# CanarySchematic3_0.net
KiCad netlist of a schematic drawn in EAGLE
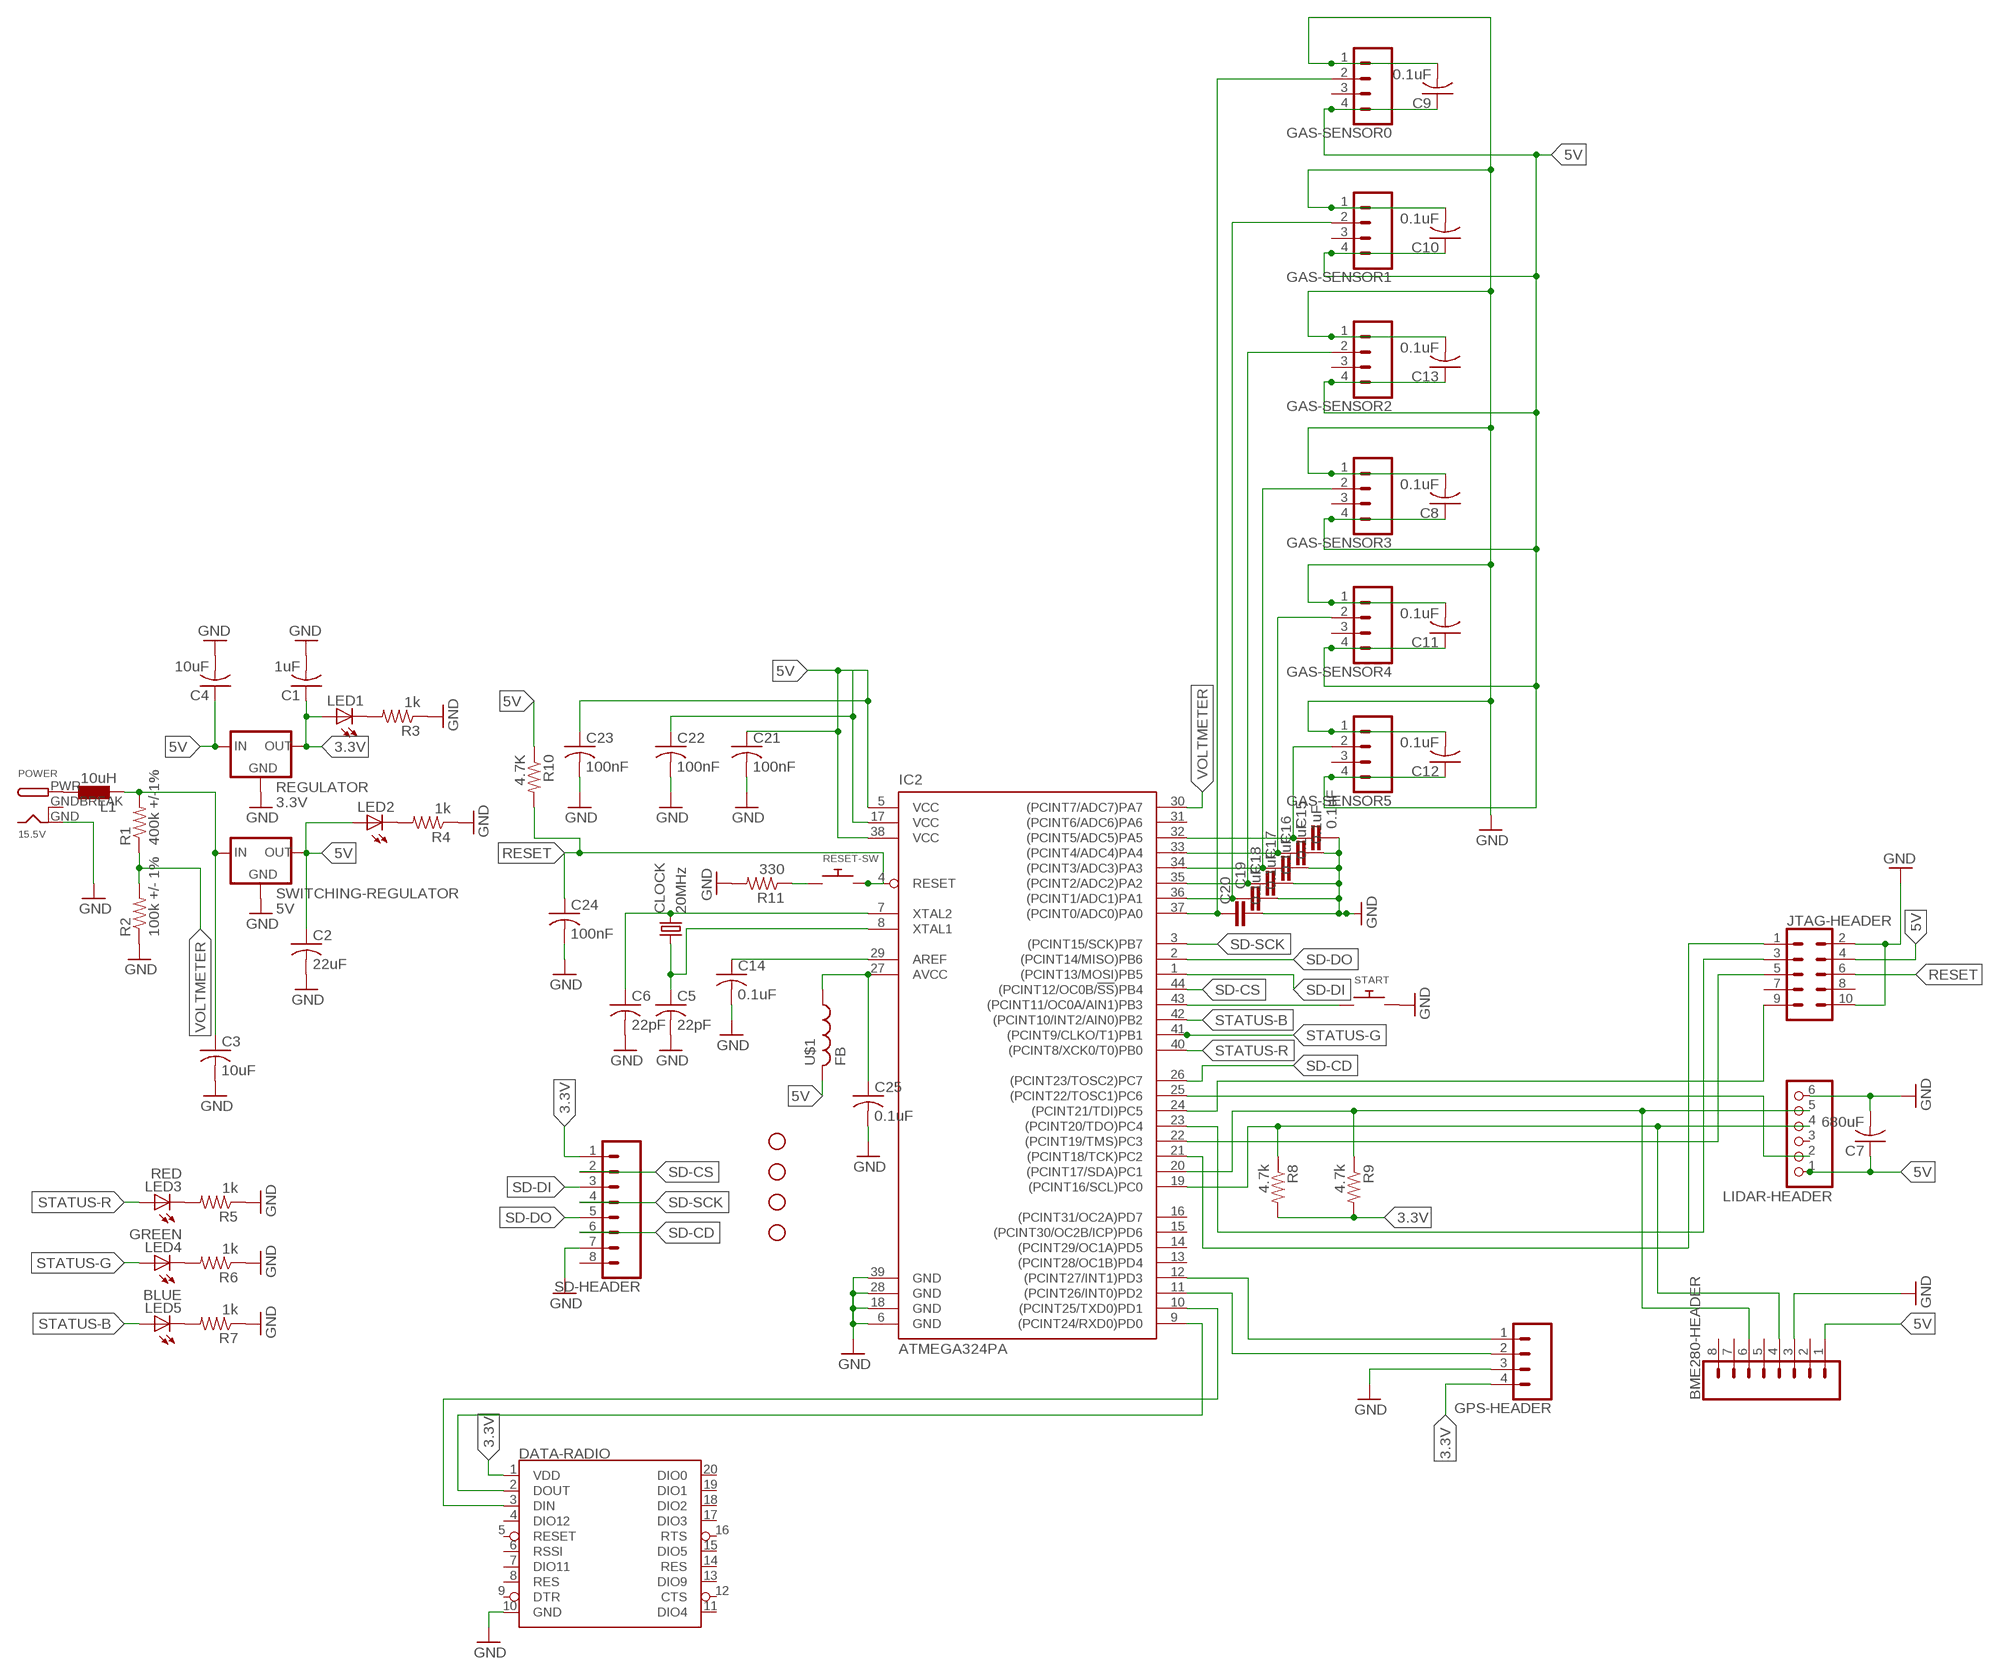
[diagram p0: schematic, sheet 1]

(export (version "E")
  (design (tool "Eeschema 10.0.6"))
  (components
    (comp (ref "BME280-HEADER")
      (value "CONN_08\"")
      (footprint "eagle-import:1X08")
      (libsource (lib "eagle-import") (part "CONN_08{dblquote}"))
    )
    (comp (ref "C1")
      (value "1uF")
      (footprint "eagle-import:C0805")
      (libsource (lib "eagle-import") (part "C-USC0805"))
    )
    (comp (ref "C2")
      (value "22uF")
      (footprint "eagle-import:C0805")
      (libsource (lib "eagle-import") (part "C-USC0805"))
    )
    (comp (ref "C3")
      (value "10uF")
      (footprint "eagle-import:C0805")
      (libsource (lib "eagle-import") (part "C-USC0805"))
    )
    (comp (ref "C4")
      (value "10uF")
      (footprint "eagle-import:C0805")
      (libsource (lib "eagle-import") (part "C-USC0805"))
    )
    (comp (ref "C5")
      (value "22pF")
      (footprint "eagle-import:C0805")
      (libsource (lib "eagle-import") (part "C-USC0805"))
    )
    (comp (ref "C6")
      (value "22pF")
      (footprint "eagle-import:C0805")
      (libsource (lib "eagle-import") (part "C-USC0805"))
    )
    (comp (ref "C7")
      (value "680uF")
      (footprint "eagle-import:C0805")
      (libsource (lib "eagle-import") (part "C-USC0805"))
    )
    (comp (ref "C8")
      (value "0.1uF")
      (footprint "eagle-import:C0805")
      (libsource (lib "eagle-import") (part "C-USC0805"))
    )
    (comp (ref "C9")
      (value "0.1uF")
      (footprint "eagle-import:C0805")
      (libsource (lib "eagle-import") (part "C-USC0805"))
    )
    (comp (ref "C10")
      (value "0.1uF")
      (footprint "eagle-import:C0805")
      (libsource (lib "eagle-import") (part "C-USC0805"))
    )
    (comp (ref "C11")
      (value "0.1uF")
      (footprint "eagle-import:C0805")
      (libsource (lib "eagle-import") (part "C-USC0805"))
    )
    (comp (ref "C12")
      (value "0.1uF")
      (footprint "eagle-import:C0805")
      (libsource (lib "eagle-import") (part "C-USC0805"))
    )
    (comp (ref "C13")
      (value "0.1uF")
      (footprint "eagle-import:C0805")
      (libsource (lib "eagle-import") (part "C-USC0805"))
    )
    (comp (ref "C14")
      (value "0.1uF")
      (footprint "eagle-import:C0805")
      (libsource (lib "eagle-import") (part "C-USC0805"))
    )
    (comp (ref "C15")
      (value "0.1uF")
      (footprint "eagle-import:C0504")
      (libsource (lib "eagle-import") (part "CC0504"))
    )
    (comp (ref "C16")
      (value "0.1uF")
      (footprint "eagle-import:C0504")
      (libsource (lib "eagle-import") (part "CC0504"))
    )
    (comp (ref "C17")
      (value "0.1uF")
      (footprint "eagle-import:C0504")
      (libsource (lib "eagle-import") (part "CC0504"))
    )
    (comp (ref "C18")
      (value "0.1uF")
      (footprint "eagle-import:C0504")
      (libsource (lib "eagle-import") (part "CC0504"))
    )
    (comp (ref "C19")
      (value "0.1uF")
      (footprint "eagle-import:C0504")
      (libsource (lib "eagle-import") (part "CC0504"))
    )
    (comp (ref "C20")
      (value "0.1uF")
      (footprint "eagle-import:C0504")
      (libsource (lib "eagle-import") (part "CC0504"))
    )
    (comp (ref "C21")
      (value "100nF")
      (footprint "eagle-import:C0805")
      (libsource (lib "eagle-import") (part "C-USC0805"))
    )
    (comp (ref "C22")
      (value "100nF")
      (footprint "eagle-import:C0805")
      (libsource (lib "eagle-import") (part "C-USC0805"))
    )
    (comp (ref "C23")
      (value "100nF")
      (footprint "eagle-import:C0805")
      (libsource (lib "eagle-import") (part "C-USC0805"))
    )
    (comp (ref "C24")
      (value "100nF")
      (footprint "eagle-import:C0805")
      (libsource (lib "eagle-import") (part "C-USC0805"))
    )
    (comp (ref "C25")
      (value "0.1uF")
      (footprint "eagle-import:C0805")
      (libsource (lib "eagle-import") (part "C-USC0805"))
    )
    (comp (ref "CLOCK")
      (value "20MHz")
      (footprint "eagle-import:86SMX")
      (libsource (lib "eagle-import") (part "CRYSTAL68SMX"))
    )
    (comp (ref "DATA-RADIO")
      (value "XBEE")
      (footprint "eagle-import:XBEE")
      (libsource (lib "eagle-import") (part "XBEE"))
    )
    (comp (ref "GAS-SENSOR0")
      (value "CONN_04")
      (footprint "eagle-import:1X04")
      (libsource (lib "eagle-import") (part "CONN_04"))
    )
    (comp (ref "GAS-SENSOR1")
      (value "CONN_04")
      (footprint "eagle-import:1X04")
      (libsource (lib "eagle-import") (part "CONN_04"))
    )
    (comp (ref "GAS-SENSOR2")
      (value "CONN_04")
      (footprint "eagle-import:1X04")
      (libsource (lib "eagle-import") (part "CONN_04"))
    )
    (comp (ref "GAS-SENSOR3")
      (value "CONN_04")
      (footprint "eagle-import:1X04")
      (libsource (lib "eagle-import") (part "CONN_04"))
    )
    (comp (ref "GAS-SENSOR4")
      (value "CONN_04")
      (footprint "eagle-import:1X04")
      (libsource (lib "eagle-import") (part "CONN_04"))
    )
    (comp (ref "GAS-SENSOR5")
      (value "CONN_04")
      (footprint "eagle-import:1X04")
      (libsource (lib "eagle-import") (part "CONN_04"))
    )
    (comp (ref "GPS-HEADER")
      (value "CONN_04")
      (footprint "eagle-import:1X04")
      (libsource (lib "eagle-import") (part "CONN_04"))
    )
    (comp (ref "H8")
      (value "STAND-OFF")
      (footprint "eagle-import:STAND-OFF")
      (libsource (lib "eagle-import") (part "STAND-OFF"))
    )
    (comp (ref "IC2")
      (value "ATMEGA324PA")
      (footprint "eagle-import:TQFP44")
      (fields (field (name "MPN") "ATMEGA644PV-10AU"))
      (libsource (lib "eagle-import") (part "ATMEGA644A"))
    )
    (comp (ref "JTAG-HEADER")
      (value "CONN_05X2PTH")
      (footprint "eagle-import:2X5")
      (libsource (lib "eagle-import") (part "CONN_05X2PTH"))
    )
    (comp (ref "L1")
      (value "10uH")
      (footprint "eagle-import:L1812")
      (libsource (lib "eagle-import") (part "L"))
    )
    (comp (ref "LED1")
      (value "LEDCHIP-LED0805")
      (footprint "eagle-import:CHIP-LED0805")
      (libsource (lib "eagle-import") (part "LEDCHIP-LED0805"))
    )
    (comp (ref "LED2")
      (value "LEDCHIP-LED0805")
      (footprint "eagle-import:CHIP-LED0805")
      (libsource (lib "eagle-import") (part "LEDCHIP-LED0805"))
    )
    (comp (ref "LED3")
      (value "RED")
      (footprint "eagle-import:CHIP-LED0805")
      (libsource (lib "eagle-import") (part "LEDCHIP-LED0805"))
    )
    (comp (ref "LED4")
      (value "GREEN")
      (footprint "eagle-import:CHIP-LED0805")
      (libsource (lib "eagle-import") (part "LEDCHIP-LED0805"))
    )
    (comp (ref "LED5")
      (value "BLUE")
      (footprint "eagle-import:CHIP-LED0805")
      (libsource (lib "eagle-import") (part "LEDCHIP-LED0805"))
    )
    (comp (ref "LIDAR-HEADER")
      (value "PINHD-1X6")
      (footprint "eagle-import:1X06")
      (libsource (lib "eagle-import") (part "PINHD-1X6"))
    )
    (comp (ref "MOUNT-HOLE1")
      (value "STAND-OFF")
      (footprint "eagle-import:STAND-OFF")
      (libsource (lib "eagle-import") (part "STAND-OFF"))
    )
    (comp (ref "MOUNT-HOLE2")
      (value "STAND-OFF")
      (footprint "eagle-import:STAND-OFF")
      (libsource (lib "eagle-import") (part "STAND-OFF"))
    )
    (comp (ref "MOUNT-HOLE3")
      (value "STAND-OFF")
      (footprint "eagle-import:STAND-OFF")
      (libsource (lib "eagle-import") (part "STAND-OFF"))
    )
    (comp (ref "POWER")
      (value "15.5V")
      (footprint "eagle-import:DCJACK_2MM_PTH")
      (libsource (lib "eagle-import") (part "DCBARRELPTH"))
    )
    (comp (ref "R1")
      (value "400k +/-1%")
      (footprint "eagle-import:M0805")
      (libsource (lib "eagle-import") (part "R-US_M0805"))
    )
    (comp (ref "R2")
      (value "100k +/- 1%")
      (footprint "eagle-import:M0805")
      (libsource (lib "eagle-import") (part "R-US_M0805"))
    )
    (comp (ref "R3")
      (value "1k")
      (footprint "eagle-import:M0805")
      (libsource (lib "eagle-import") (part "R-US_M0805"))
    )
    (comp (ref "R4")
      (value "1k")
      (footprint "eagle-import:M0805")
      (libsource (lib "eagle-import") (part "R-US_M0805"))
    )
    (comp (ref "R5")
      (value "1k")
      (footprint "eagle-import:M0805")
      (libsource (lib "eagle-import") (part "R-US_M0805"))
    )
    (comp (ref "R6")
      (value "1k")
      (footprint "eagle-import:M0805")
      (libsource (lib "eagle-import") (part "R-US_M0805"))
    )
    (comp (ref "R7")
      (value "1k")
      (footprint "eagle-import:M0805")
      (libsource (lib "eagle-import") (part "R-US_M0805"))
    )
    (comp (ref "R8")
      (value "4.7k")
      (footprint "eagle-import:M0805")
      (libsource (lib "eagle-import") (part "R-US_M0805"))
    )
    (comp (ref "R9")
      (value "4.7k")
      (footprint "eagle-import:M0805")
      (libsource (lib "eagle-import") (part "R-US_M0805"))
    )
    (comp (ref "R10")
      (value "4.7K")
      (footprint "eagle-import:M0805")
      (libsource (lib "eagle-import") (part "R-US_M0805"))
    )
    (comp (ref "R11")
      (value "330")
      (footprint "eagle-import:M0805")
      (libsource (lib "eagle-import") (part "R-US_M0805"))
    )
    (comp (ref "REGULATOR")
      (value "3.3V")
      (footprint "eagle-import:TO220-IGO")
      (libsource (lib "eagle-import") (part "V_REG_78XXSINK"))
    )
    (comp (ref "RESET-SW")
      (value "SWITCH_PUSHBUTTONSOFTTOUCHSMD_SJ")
      (footprint "eagle-import:PUSHBUTTON_SMD_SJ")
      (libsource (lib "eagle-import") (part "SWITCH_PUSHBUTTONSOFTTOUCHSMD_SJ"))
    )
    (comp (ref "SD-HEADER")
      (value "CONN_08\"")
      (footprint "eagle-import:1X08")
      (libsource (lib "eagle-import") (part "CONN_08{dblquote}"))
    )
    (comp (ref "START")
      (value "SWITCH_PUSHBUTTONSOFTTOUCHSMD_SJ")
      (footprint "eagle-import:PUSHBUTTON_SMD_SJ")
      (libsource (lib "eagle-import") (part "SWITCH_PUSHBUTTONSOFTTOUCHSMD_SJ"))
    )
    (comp (ref "SWITCHING-REGULATOR")
      (value "5V")
      (footprint "eagle-import:TO220-IGO")
      (libsource (lib "eagle-import") (part "V_REG_78XXSINK"))
    )
    (comp (ref "U$1") (value "FB") (footprint "eagle-import:FB") (libsource (lib "eagle-import") (part "FB")))
  )
  (nets
    (net (code "1") (name "/GNDBREAK") (class "Default")
      (node (ref "POWER") (pin "GNDBREAK") (pinfunction "GNDBREAK_GNDBREAK") (pintype "power_in"))
    )
    (net (code "2") (name "3.3V") (class "Default")
      (node (ref "C1") (pin "1") (pinfunction "1_1") (pintype "passive"))
      (node (ref "DATA-RADIO") (pin "1") (pinfunction "VDD_1") (pintype "power_in"))
      (node (ref "GPS-HEADER") (pin "4") (pinfunction "4_4") (pintype "passive"))
      (node (ref "LED1") (pin "A") (pinfunction "A_A") (pintype "passive"))
      (node (ref "R8") (pin "2") (pinfunction "2_2") (pintype "passive"))
      (node (ref "R9") (pin "2") (pinfunction "2_2") (pintype "passive"))
      (node (ref "REGULATOR") (pin "OUT") (pinfunction "OUT_OUT") (pintype "passive"))
      (node (ref "SD-HEADER") (pin "1") (pinfunction "1_1") (pintype "passive"))
    )
    (net (code "3") (name "5V") (class "Default")
      (node (ref "BME280-HEADER") (pin "1") (pinfunction "1_1") (pintype "passive"))
      (node (ref "C10") (pin "1") (pinfunction "1_1") (pintype "passive"))
      (node (ref "C11") (pin "1") (pinfunction "1_1") (pintype "passive"))
      (node (ref "C12") (pin "1") (pinfunction "1_1") (pintype "passive"))
      (node (ref "C13") (pin "1") (pinfunction "1_1") (pintype "passive"))
      (node (ref "C2") (pin "1") (pinfunction "1_1") (pintype "passive"))
      (node (ref "C25") (pin "1") (pinfunction "1_1") (pintype "passive"))
      (node (ref "C4") (pin "1") (pinfunction "1_1") (pintype "passive"))
      (node (ref "C7") (pin "1") (pinfunction "1_1") (pintype "passive"))
      (node (ref "C8") (pin "1") (pinfunction "1_1") (pintype "passive"))
      (node (ref "C9") (pin "1") (pinfunction "1_1") (pintype "passive"))
      (node (ref "GAS-SENSOR0") (pin "4") (pinfunction "4_4") (pintype "passive"))
      (node (ref "GAS-SENSOR1") (pin "4") (pinfunction "4_4") (pintype "passive"))
      (node (ref "GAS-SENSOR2") (pin "4") (pinfunction "4_4") (pintype "passive"))
      (node (ref "GAS-SENSOR3") (pin "4") (pinfunction "4_4") (pintype "passive"))
      (node (ref "GAS-SENSOR4") (pin "4") (pinfunction "4_4") (pintype "passive"))
      (node (ref "GAS-SENSOR5") (pin "4") (pinfunction "4_4") (pintype "passive"))
      (node (ref "IC2") (pin "27") (pinfunction "AVCC_27") (pintype "power_in"))
      (node (ref "JTAG-HEADER") (pin "4") (pinfunction "4_4") (pintype "passive"))
      (node (ref "LED2") (pin "A") (pinfunction "A_A") (pintype "passive"))
      (node (ref "LIDAR-HEADER") (pin "1") (pinfunction "1_1") (pintype "passive"))
      (node (ref "REGULATOR") (pin "IN") (pinfunction "IN_IN") (pintype "input"))
      (node (ref "SWITCHING-REGULATOR") (pin "OUT") (pinfunction "OUT_OUT") (pintype "passive"))
      (node (ref "U$1") (pin "P$1") (pinfunction "1_P$1") (pintype "passive"))
    )
    (net (code "4") (name "GND") (class "Default")
      (node (ref "BME280-HEADER") (pin "3") (pinfunction "3_3") (pintype "passive"))
      (node (ref "C1") (pin "2") (pinfunction "2_2") (pintype "passive"))
      (node (ref "C10") (pin "2") (pinfunction "2_2") (pintype "passive"))
      (node (ref "C11") (pin "2") (pinfunction "2_2") (pintype "passive"))
      (node (ref "C12") (pin "2") (pinfunction "2_2") (pintype "passive"))
      (node (ref "C13") (pin "2") (pinfunction "2_2") (pintype "passive"))
      (node (ref "C14") (pin "2") (pinfunction "2_2") (pintype "passive"))
      (node (ref "C15") (pin "2") (pinfunction "2_2") (pintype "passive"))
      (node (ref "C16") (pin "2") (pinfunction "2_2") (pintype "passive"))
      (node (ref "C17") (pin "2") (pinfunction "2_2") (pintype "passive"))
      (node (ref "C18") (pin "2") (pinfunction "2_2") (pintype "passive"))
      (node (ref "C19") (pin "2") (pinfunction "2_2") (pintype "passive"))
      (node (ref "C2") (pin "2") (pinfunction "2_2") (pintype "passive"))
      (node (ref "C20") (pin "2") (pinfunction "2_2") (pintype "passive"))
      (node (ref "C21") (pin "2") (pinfunction "2_2") (pintype "passive"))
      (node (ref "C22") (pin "2") (pinfunction "2_2") (pintype "passive"))
      (node (ref "C23") (pin "2") (pinfunction "2_2") (pintype "passive"))
      (node (ref "C24") (pin "2") (pinfunction "2_2") (pintype "passive"))
      (node (ref "C25") (pin "2") (pinfunction "2_2") (pintype "passive"))
      (node (ref "C3") (pin "2") (pinfunction "2_2") (pintype "passive"))
      (node (ref "C4") (pin "2") (pinfunction "2_2") (pintype "passive"))
      (node (ref "C5") (pin "2") (pinfunction "2_2") (pintype "passive"))
      (node (ref "C6") (pin "2") (pinfunction "2_2") (pintype "passive"))
      (node (ref "C7") (pin "2") (pinfunction "2_2") (pintype "passive"))
      (node (ref "C8") (pin "2") (pinfunction "2_2") (pintype "passive"))
      (node (ref "C9") (pin "2") (pinfunction "2_2") (pintype "passive"))
      (node (ref "DATA-RADIO") (pin "10") (pinfunction "GND_10") (pintype "power_in"))
      (node (ref "GAS-SENSOR0") (pin "1") (pinfunction "1_1") (pintype "passive"))
      (node (ref "GAS-SENSOR1") (pin "1") (pinfunction "1_1") (pintype "passive"))
      (node (ref "GAS-SENSOR2") (pin "1") (pinfunction "1_1") (pintype "passive"))
      (node (ref "GAS-SENSOR3") (pin "1") (pinfunction "1_1") (pintype "passive"))
      (node (ref "GAS-SENSOR4") (pin "1") (pinfunction "1_1") (pintype "passive"))
      (node (ref "GAS-SENSOR5") (pin "1") (pinfunction "1_1") (pintype "passive"))
      (node (ref "GPS-HEADER") (pin "3") (pinfunction "3_3") (pintype "passive"))
      (node (ref "IC2") (pin "18") (pinfunction "GND_18") (pintype "power_in"))
      (node (ref "IC2") (pin "28") (pinfunction "GND_28") (pintype "power_in"))
      (node (ref "IC2") (pin "39") (pinfunction "GND_39") (pintype "power_in"))
      (node (ref "IC2") (pin "6") (pinfunction "GND_6") (pintype "power_in"))
      (node (ref "JTAG-HEADER") (pin "10") (pinfunction "10_10") (pintype "passive"))
      (node (ref "JTAG-HEADER") (pin "2") (pinfunction "2_2") (pintype "passive"))
      (node (ref "LIDAR-HEADER") (pin "6") (pinfunction "6_6") (pintype "passive"))
      (node (ref "POWER") (pin "GND") (pinfunction "GND_GND") (pintype "power_in"))
      (node (ref "R11") (pin "2") (pinfunction "2_2") (pintype "passive"))
      (node (ref "R2") (pin "1") (pinfunction "1_1") (pintype "passive"))
      (node (ref "R3") (pin "1") (pinfunction "1_1") (pintype "passive"))
      (node (ref "R4") (pin "1") (pinfunction "1_1") (pintype "passive"))
      (node (ref "R5") (pin "1") (pinfunction "1_1") (pintype "passive"))
      (node (ref "R6") (pin "1") (pinfunction "1_1") (pintype "passive"))
      (node (ref "R7") (pin "1") (pinfunction "1_1") (pintype "passive"))
      (node (ref "REGULATOR") (pin "GND") (pinfunction "GND_GND") (pintype "input"))
      (node (ref "SD-HEADER") (pin "7") (pinfunction "7_7") (pintype "passive"))
      (node (ref "START") (pin "P$2") (pinfunction "P$2_P$2") (pintype "passive"))
      (node (ref "SWITCHING-REGULATOR") (pin "GND") (pinfunction "GND_GND") (pintype "input"))
    )
    (net (code "5") (name "Net-(C3-Pad1)") (class "Default")
      (node (ref "C3") (pin "1") (pinfunction "1_1") (pintype "passive"))
      (node (ref "L1") (pin "2") (pinfunction "2_2") (pintype "passive"))
      (node (ref "R1") (pin "2") (pinfunction "2_2") (pintype "passive"))
      (node (ref "SWITCHING-REGULATOR") (pin "IN") (pinfunction "IN_IN") (pintype "input"))
    )
    (net (code "6") (name "Net-(C21-Pad1)") (class "Default")
      (node (ref "C21") (pin "1") (pinfunction "1_1") (pintype "passive"))
      (node (ref "C22") (pin "1") (pinfunction "1_1") (pintype "passive"))
      (node (ref "C23") (pin "1") (pinfunction "1_1") (pintype "passive"))
      (node (ref "IC2") (pin "17") (pinfunction "VCC_17") (pintype "power_in"))
      (node (ref "IC2") (pin "38") (pinfunction "VCC_38") (pintype "power_in"))
      (node (ref "IC2") (pin "5") (pinfunction "VCC_5") (pintype "power_in"))
    )
    (net (code "7") (name "Net-(CLOCK-2)") (class "Default")
      (node (ref "C6") (pin "1") (pinfunction "1_1") (pintype "passive"))
      (node (ref "CLOCK") (pin "4") (pinfunction "2_4") (pintype "passive"))
      (node (ref "IC2") (pin "7") (pinfunction "XTAL2_7") (pintype "bidirectional"))
    )
    (net (code "8") (name "Net-(DATA-RADIO-DIN)") (class "Default")
      (node (ref "DATA-RADIO") (pin "3") (pinfunction "DIN_3") (pintype "input"))
      (node (ref "IC2") (pin "10") (pinfunction "(PCINT25/TXD0)PD1_10") (pintype "bidirectional"))
    )
    (net (code "9") (name "Net-(DATA-RADIO-DOUT)") (class "Default")
      (node (ref "DATA-RADIO") (pin "2") (pinfunction "DOUT_2") (pintype "output"))
      (node (ref "IC2") (pin "9") (pinfunction "(PCINT24/RXD0)PD0_9") (pintype "bidirectional"))
    )
    (net (code "10") (name "Net-(IC2-(PCINT0{slash}ADC0)PA0)") (class "Default")
      (node (ref "C20") (pin "1") (pinfunction "1_1") (pintype "passive"))
      (node (ref "GAS-SENSOR0") (pin "2") (pinfunction "2_2") (pintype "passive"))
      (node (ref "IC2") (pin "37") (pinfunction "(PCINT0/ADC0)PA0_37") (pintype "bidirectional"))
    )
    (net (code "11") (name "Net-(IC2-(PCINT1{slash}ADC1)PA1)") (class "Default")
      (node (ref "C19") (pin "1") (pinfunction "1_1") (pintype "passive"))
      (node (ref "GAS-SENSOR1") (pin "2") (pinfunction "2_2") (pintype "passive"))
      (node (ref "IC2") (pin "36") (pinfunction "(PCINT1/ADC1)PA1_36") (pintype "bidirectional"))
    )
    (net (code "12") (name "Net-(IC2-(PCINT2{slash}ADC2)PA2)") (class "Default")
      (node (ref "C18") (pin "1") (pinfunction "1_1") (pintype "passive"))
      (node (ref "GAS-SENSOR2") (pin "2") (pinfunction "2_2") (pintype "passive"))
      (node (ref "IC2") (pin "35") (pinfunction "(PCINT2/ADC2)PA2_35") (pintype "bidirectional"))
    )
    (net (code "13") (name "Net-(IC2-(PCINT3{slash}ADC3)PA3)") (class "Default")
      (node (ref "C17") (pin "1") (pinfunction "1_1") (pintype "passive"))
      (node (ref "GAS-SENSOR3") (pin "2") (pinfunction "2_2") (pintype "passive"))
      (node (ref "IC2") (pin "34") (pinfunction "(PCINT3/ADC3)PA3_34") (pintype "bidirectional"))
    )
    (net (code "14") (name "Net-(IC2-(PCINT4{slash}ADC4)PA4)") (class "Default")
      (node (ref "C16") (pin "1") (pinfunction "1_1") (pintype "passive"))
      (node (ref "GAS-SENSOR4") (pin "2") (pinfunction "2_2") (pintype "passive"))
      (node (ref "IC2") (pin "33") (pinfunction "(PCINT4/ADC4)PA4_33") (pintype "bidirectional"))
    )
    (net (code "15") (name "Net-(IC2-(PCINT5{slash}ADC5)PA5)") (class "Default")
      (node (ref "C15") (pin "1") (pinfunction "1_1") (pintype "passive"))
      (node (ref "GAS-SENSOR5") (pin "2") (pinfunction "2_2") (pintype "passive"))
      (node (ref "IC2") (pin "32") (pinfunction "(PCINT5/ADC5)PA5_32") (pintype "bidirectional"))
    )
    (net (code "16") (name "Net-(IC2-(PCINT11{slash}OC0A{slash}AIN1)PB3)") (class "Default")
      (node (ref "IC2") (pin "43") (pinfunction "(PCINT11/OC0A/AIN1)PB3_43") (pintype "bidirectional"))
      (node (ref "START") (pin "P$1") (pinfunction "P$1_P$1") (pintype "passive"))
    )
    (net (code "17") (name "Net-(IC2-(PCINT16{slash}SCL)PC0)") (class "Default")
      (node (ref "BME280-HEADER") (pin "4") (pinfunction "4_4") (pintype "passive"))
      (node (ref "IC2") (pin "19") (pinfunction "(PCINT16/SCL)PC0_19") (pintype "output"))
      (node (ref "LIDAR-HEADER") (pin "4") (pinfunction "4_4") (pintype "passive"))
      (node (ref "R8") (pin "1") (pinfunction "1_1") (pintype "passive"))
    )
    (net (code "18") (name "Net-(IC2-(PCINT17{slash}SDA)PC1)") (class "Default")
      (node (ref "BME280-HEADER") (pin "6") (pinfunction "6_6") (pintype "passive"))
      (node (ref "IC2") (pin "20") (pinfunction "(PCINT17/SDA)PC1_20") (pintype "output"))
      (node (ref "LIDAR-HEADER") (pin "5") (pinfunction "5_5") (pintype "passive"))
      (node (ref "R9") (pin "1") (pinfunction "1_1") (pintype "passive"))
    )
    (net (code "19") (name "Net-(IC2-(PCINT18{slash}TCK)PC2)") (class "Default")
      (node (ref "IC2") (pin "21") (pinfunction "(PCINT18/TCK)PC2_21") (pintype "output"))
      (node (ref "JTAG-HEADER") (pin "1") (pinfunction "1_1") (pintype "passive"))
    )
    (net (code "20") (name "Net-(IC2-(PCINT19{slash}TMS)PC3)") (class "Default")
      (node (ref "IC2") (pin "22") (pinfunction "(PCINT19/TMS)PC3_22") (pintype "output"))
      (node (ref "JTAG-HEADER") (pin "5") (pinfunction "5_5") (pintype "passive"))
    )
    (net (code "21") (name "Net-(IC2-(PCINT20{slash}TDO)PC4)") (class "Default")
      (node (ref "IC2") (pin "23") (pinfunction "(PCINT20/TDO)PC4_23") (pintype "output"))
      (node (ref "JTAG-HEADER") (pin "3") (pinfunction "3_3") (pintype "passive"))
    )
    (net (code "22") (name "Net-(IC2-(PCINT21{slash}TDI)PC5)") (class "Default")
      (node (ref "IC2") (pin "24") (pinfunction "(PCINT21/TDI)PC5_24") (pintype "output"))
      (node (ref "JTAG-HEADER") (pin "9") (pinfunction "9_9") (pintype "passive"))
    )
    (net (code "23") (name "Net-(IC2-(PCINT22{slash}TOSC1)PC6)") (class "Default")
      (node (ref "IC2") (pin "25") (pinfunction "(PCINT22/TOSC1)PC6_25") (pintype "output"))
      (node (ref "LIDAR-HEADER") (pin "2") (pinfunction "2_2") (pintype "passive"))
    )
    (net (code "24") (name "Net-(IC2-(PCINT26{slash}INT0)PD2)") (class "Default")
      (node (ref "GPS-HEADER") (pin "2") (pinfunction "2_2") (pintype "passive"))
      (node (ref "IC2") (pin "11") (pinfunction "(PCINT26/INT0)PD2_11") (pintype "bidirectional"))
    )
    (net (code "25") (name "Net-(IC2-(PCINT27{slash}INT1)PD3)") (class "Default")
      (node (ref "GPS-HEADER") (pin "1") (pinfunction "1_1") (pintype "passive"))
      (node (ref "IC2") (pin "12") (pinfunction "(PCINT27/INT1)PD3_12") (pintype "bidirectional"))
    )
    (net (code "26") (name "Net-(IC2-AREF)") (class "Default")
      (node (ref "C14") (pin "1") (pinfunction "1_1") (pintype "passive"))
      (node (ref "IC2") (pin "29") (pinfunction "AREF_29") (pintype "passive"))
    )
    (net (code "27") (name "Net-(IC2-XTAL1)") (class "Default")
      (node (ref "C5") (pin "1") (pinfunction "1_1") (pintype "passive"))
      (node (ref "CLOCK") (pin "1") (pinfunction "1_1") (pintype "passive"))
      (node (ref "IC2") (pin "8") (pinfunction "XTAL1_8") (pintype "bidirectional"))
    )
    (net (code "28") (name "Net-(L1-Pad1)") (class "Default")
      (node (ref "L1") (pin "1") (pinfunction "1_1") (pintype "passive"))
      (node (ref "POWER") (pin "PWR") (pinfunction "PWR_PWR") (pintype "power_in"))
    )
    (net (code "29") (name "Net-(LED1-PadC)") (class "Default")
      (node (ref "LED1") (pin "C") (pinfunction "C_C") (pintype "passive"))
      (node (ref "R3") (pin "2") (pinfunction "2_2") (pintype "passive"))
    )
    (net (code "30") (name "Net-(LED2-PadC)") (class "Default")
      (node (ref "LED2") (pin "C") (pinfunction "C_C") (pintype "passive"))
      (node (ref "R4") (pin "2") (pinfunction "2_2") (pintype "passive"))
    )
    (net (code "31") (name "Net-(LED3-PadC)") (class "Default")
      (node (ref "LED3") (pin "C") (pinfunction "C_C") (pintype "passive"))
      (node (ref "R5") (pin "2") (pinfunction "2_2") (pintype "passive"))
    )
    (net (code "32") (name "Net-(LED4-PadC)") (class "Default")
      (node (ref "LED4") (pin "C") (pinfunction "C_C") (pintype "passive"))
      (node (ref "R6") (pin "2") (pinfunction "2_2") (pintype "passive"))
    )
    (net (code "33") (name "Net-(LED5-PadC)") (class "Default")
      (node (ref "LED5") (pin "C") (pinfunction "C_C") (pintype "passive"))
      (node (ref "R7") (pin "2") (pinfunction "2_2") (pintype "passive"))
    )
    (net (code "34") (name "Net-(R11-Pad1)") (class "Default")
      (node (ref "R11") (pin "1") (pinfunction "1_1") (pintype "passive"))
      (node (ref "RESET-SW") (pin "P$1") (pinfunction "P$1_P$1") (pintype "passive"))
    )
    (net (code "35") (name "RESET") (class "Default")
      (node (ref "C24") (pin "1") (pinfunction "1_1") (pintype "passive"))
      (node (ref "IC2") (pin "4") (pinfunction "RESET_4") (pintype "input"))
      (node (ref "JTAG-HEADER") (pin "6") (pinfunction "6_6") (pintype "passive"))
      (node (ref "R10") (pin "2") (pinfunction "2_2") (pintype "passive"))
      (node (ref "RESET-SW") (pin "P$2") (pinfunction "P$2_P$2") (pintype "passive"))
    )
    (net (code "36") (name "SD-CD") (class "Default")
      (node (ref "IC2") (pin "26") (pinfunction "(PCINT23/TOSC2)PC7_26") (pintype "output"))
      (node (ref "SD-HEADER") (pin "6") (pinfunction "6_6") (pintype "passive"))
    )
    (net (code "37") (name "SD-CS") (class "Default")
      (node (ref "IC2") (pin "44") (pinfunction "(PCINT12/OC0B/~{SS})PB4_44") (pintype "bidirectional"))
      (node (ref "SD-HEADER") (pin "2") (pinfunction "2_2") (pintype "passive"))
    )
    (net (code "38") (name "SD-DI") (class "Default")
      (node (ref "IC2") (pin "1") (pinfunction "(PCINT13/MOSI)PB5_1") (pintype "bidirectional"))
      (node (ref "SD-HEADER") (pin "3") (pinfunction "3_3") (pintype "passive"))
    )
    (net (code "39") (name "SD-DO") (class "Default")
      (node (ref "IC2") (pin "2") (pinfunction "(PCINT14/MISO)PB6_2") (pintype "bidirectional"))
      (node (ref "SD-HEADER") (pin "5") (pinfunction "5_5") (pintype "passive"))
    )
    (net (code "40") (name "SD-SCK") (class "Default")
      (node (ref "IC2") (pin "3") (pinfunction "(PCINT15/SCK)PB7_3") (pintype "bidirectional"))
      (node (ref "SD-HEADER") (pin "4") (pinfunction "4_4") (pintype "passive"))
    )
    (net (code "41") (name "STATUS-B") (class "Default")
      (node (ref "IC2") (pin "42") (pinfunction "(PCINT10/INT2/AIN0)PB2_42") (pintype "bidirectional"))
      (node (ref "LED5") (pin "A") (pinfunction "A_A") (pintype "passive"))
    )
    (net (code "42") (name "STATUS-G") (class "Default")
      (node (ref "IC2") (pin "41") (pinfunction "(PCINT9/CLKO/T1)PB1_41") (pintype "bidirectional"))
      (node (ref "LED4") (pin "A") (pinfunction "A_A") (pintype "passive"))
    )
    (net (code "43") (name "STATUS-R") (class "Default")
      (node (ref "IC2") (pin "40") (pinfunction "(PCINT8/XCK0/T0)PB0_40") (pintype "bidirectional"))
      (node (ref "LED3") (pin "A") (pinfunction "A_A") (pintype "passive"))
    )
    (net (code "44") (name "VOLTMETER") (class "Default")
      (node (ref "IC2") (pin "30") (pinfunction "(PCINT7/ADC7)PA7_30") (pintype "bidirectional"))
      (node (ref "R1") (pin "1") (pinfunction "1_1") (pintype "passive"))
      (node (ref "R2") (pin "2") (pinfunction "2_2") (pintype "passive"))
    )
    (net (code "45") (name "unconnected-(BME280-HEADER-Pad2)") (class "Default")
      (node (ref "BME280-HEADER") (pin "2") (pinfunction "2_2") (pintype "passive"))
    )
    (net (code "46") (name "unconnected-(BME280-HEADER-Pad5)") (class "Default")
      (node (ref "BME280-HEADER") (pin "5") (pinfunction "5_5") (pintype "passive"))
    )
    (net (code "47") (name "unconnected-(BME280-HEADER-Pad7)") (class "Default")
      (node (ref "BME280-HEADER") (pin "7") (pinfunction "7_7") (pintype "passive"))
    )
    (net (code "48") (name "unconnected-(BME280-HEADER-Pad8)") (class "Default")
      (node (ref "BME280-HEADER") (pin "8") (pinfunction "8_8") (pintype "passive"))
    )
    (net (code "49") (name "unconnected-(DATA-RADIO-CTS-Pad12)") (class "Default")
      (node (ref "DATA-RADIO") (pin "12") (pinfunction "CTS_12") (pintype "output"))
    )
    (net (code "50") (name "unconnected-(DATA-RADIO-DIO0-Pad20)") (class "Default")
      (node (ref "DATA-RADIO") (pin "20") (pinfunction "DIO0_20") (pintype "bidirectional"))
    )
    (net (code "51") (name "unconnected-(DATA-RADIO-DIO1-Pad19)") (class "Default")
      (node (ref "DATA-RADIO") (pin "19") (pinfunction "DIO1_19") (pintype "bidirectional"))
    )
    (net (code "52") (name "unconnected-(DATA-RADIO-DIO2-Pad18)") (class "Default")
      (node (ref "DATA-RADIO") (pin "18") (pinfunction "DIO2_18") (pintype "bidirectional"))
    )
    (net (code "53") (name "unconnected-(DATA-RADIO-DIO3-Pad17)") (class "Default")
      (node (ref "DATA-RADIO") (pin "17") (pinfunction "DIO3_17") (pintype "bidirectional"))
    )
    (net (code "54") (name "unconnected-(DATA-RADIO-DIO4-Pad11)") (class "Default")
      (node (ref "DATA-RADIO") (pin "11") (pinfunction "DIO4_11") (pintype "bidirectional"))
    )
    (net (code "55") (name "unconnected-(DATA-RADIO-DIO5-Pad15)") (class "Default")
      (node (ref "DATA-RADIO") (pin "15") (pinfunction "DIO5_15") (pintype "bidirectional"))
    )
    (net (code "56") (name "unconnected-(DATA-RADIO-DIO9-Pad13)") (class "Default")
      (node (ref "DATA-RADIO") (pin "13") (pinfunction "DIO9_13") (pintype "bidirectional"))
    )
    (net (code "57") (name "unconnected-(DATA-RADIO-DIO11-Pad7)") (class "Default")
      (node (ref "DATA-RADIO") (pin "7") (pinfunction "DIO11_7") (pintype "bidirectional"))
    )
    (net (code "58") (name "unconnected-(DATA-RADIO-DIO12-Pad4)") (class "Default")
      (node (ref "DATA-RADIO") (pin "4") (pinfunction "DIO12_4") (pintype "bidirectional"))
    )
    (net (code "59") (name "unconnected-(DATA-RADIO-DTR-Pad9)") (class "Default")
      (node (ref "DATA-RADIO") (pin "9") (pinfunction "DTR_9") (pintype "bidirectional"))
    )
    (net (code "60") (name "unconnected-(DATA-RADIO-RES-Pad8)") (class "Default")
      (node (ref "DATA-RADIO") (pin "8") (pinfunction "RES_8") (pintype "bidirectional"))
    )
    (net (code "61") (name "unconnected-(DATA-RADIO-RES-Pad14)") (class "Default")
      (node (ref "DATA-RADIO") (pin "14") (pinfunction "RES_14") (pintype "bidirectional"))
    )
    (net (code "62") (name "unconnected-(DATA-RADIO-RESET-Pad5)") (class "Default")
      (node (ref "DATA-RADIO") (pin "5") (pinfunction "RESET_5") (pintype "input"))
    )
    (net (code "63") (name "unconnected-(DATA-RADIO-RSSI-Pad6)") (class "Default")
      (node (ref "DATA-RADIO") (pin "6") (pinfunction "RSSI_6") (pintype "bidirectional"))
    )
    (net (code "64") (name "unconnected-(DATA-RADIO-RTS-Pad16)") (class "Default")
      (node (ref "DATA-RADIO") (pin "16") (pinfunction "RTS_16") (pintype "input"))
    )
    (net (code "65") (name "unconnected-(GAS-SENSOR0-Pad3)") (class "Default")
      (node (ref "GAS-SENSOR0") (pin "3") (pinfunction "3_3") (pintype "passive"))
    )
    (net (code "66") (name "unconnected-(GAS-SENSOR1-Pad3)") (class "Default")
      (node (ref "GAS-SENSOR1") (pin "3") (pinfunction "3_3") (pintype "passive"))
    )
    (net (code "67") (name "unconnected-(GAS-SENSOR2-Pad3)") (class "Default")
      (node (ref "GAS-SENSOR2") (pin "3") (pinfunction "3_3") (pintype "passive"))
    )
    (net (code "68") (name "unconnected-(GAS-SENSOR3-Pad3)") (class "Default")
      (node (ref "GAS-SENSOR3") (pin "3") (pinfunction "3_3") (pintype "passive"))
    )
    (net (code "69") (name "unconnected-(GAS-SENSOR4-Pad3)") (class "Default")
      (node (ref "GAS-SENSOR4") (pin "3") (pinfunction "3_3") (pintype "passive"))
    )
    (net (code "70") (name "unconnected-(GAS-SENSOR5-Pad3)") (class "Default")
      (node (ref "GAS-SENSOR5") (pin "3") (pinfunction "3_3") (pintype "passive"))
    )
    (net (code "71") (name "unconnected-(IC2-(PCINT6{slash}ADC6)PA6-Pad31)") (class "Default")
      (node (ref "IC2") (pin "31") (pinfunction "(PCINT6/ADC6)PA6_31") (pintype "bidirectional"))
    )
    (net (code "72") (name "unconnected-(IC2-(PCINT28{slash}OC1B)PD4-Pad13)") (class "Default")
      (node (ref "IC2") (pin "13") (pinfunction "(PCINT28/OC1B)PD4_13") (pintype "bidirectional"))
    )
    (net (code "73") (name "unconnected-(IC2-(PCINT29{slash}OC1A)PD5-Pad14)") (class "Default")
      (node (ref "IC2") (pin "14") (pinfunction "(PCINT29/OC1A)PD5_14") (pintype "bidirectional"))
    )
    (net (code "74") (name "unconnected-(IC2-(PCINT30{slash}OC2B{slash}ICP)PD6-Pad15)") (class "Default")
      (node (ref "IC2") (pin "15") (pinfunction "(PCINT30/OC2B/ICP)PD6_15") (pintype "bidirectional"))
    )
    (net (code "75") (name "unconnected-(IC2-(PCINT31{slash}OC2A)PD7-Pad16)") (class "Default")
      (node (ref "IC2") (pin "16") (pinfunction "(PCINT31/OC2A)PD7_16") (pintype "bidirectional"))
    )
    (net (code "76") (name "unconnected-(JTAG-HEADER-Pad7)") (class "Default")
      (node (ref "JTAG-HEADER") (pin "7") (pinfunction "7_7") (pintype "passive"))
    )
    (net (code "77") (name "unconnected-(JTAG-HEADER-Pad8)") (class "Default")
      (node (ref "JTAG-HEADER") (pin "8") (pinfunction "8_8") (pintype "passive"))
    )
    (net (code "78") (name "unconnected-(LIDAR-HEADER-Pad3)") (class "Default")
      (node (ref "LIDAR-HEADER") (pin "3") (pinfunction "3_3") (pintype "passive"))
    )
    (net (code "79") (name "unconnected-(R10-Pad1)") (class "Default")
      (node (ref "R10") (pin "1") (pinfunction "1_1") (pintype "passive"))
    )
    (net (code "80") (name "unconnected-(SD-HEADER-Pad8)") (class "Default")
      (node (ref "SD-HEADER") (pin "8") (pinfunction "8_8") (pintype "passive"))
    )
    (net (code "81") (name "unconnected-(U$1-2-PadP$2)") (class "Default")
      (node (ref "U$1") (pin "P$2") (pinfunction "2_P$2") (pintype "passive"))
    )
  )
)
